# Sheet.net
KiCad netlist of a schematic drawn in Altium Designer
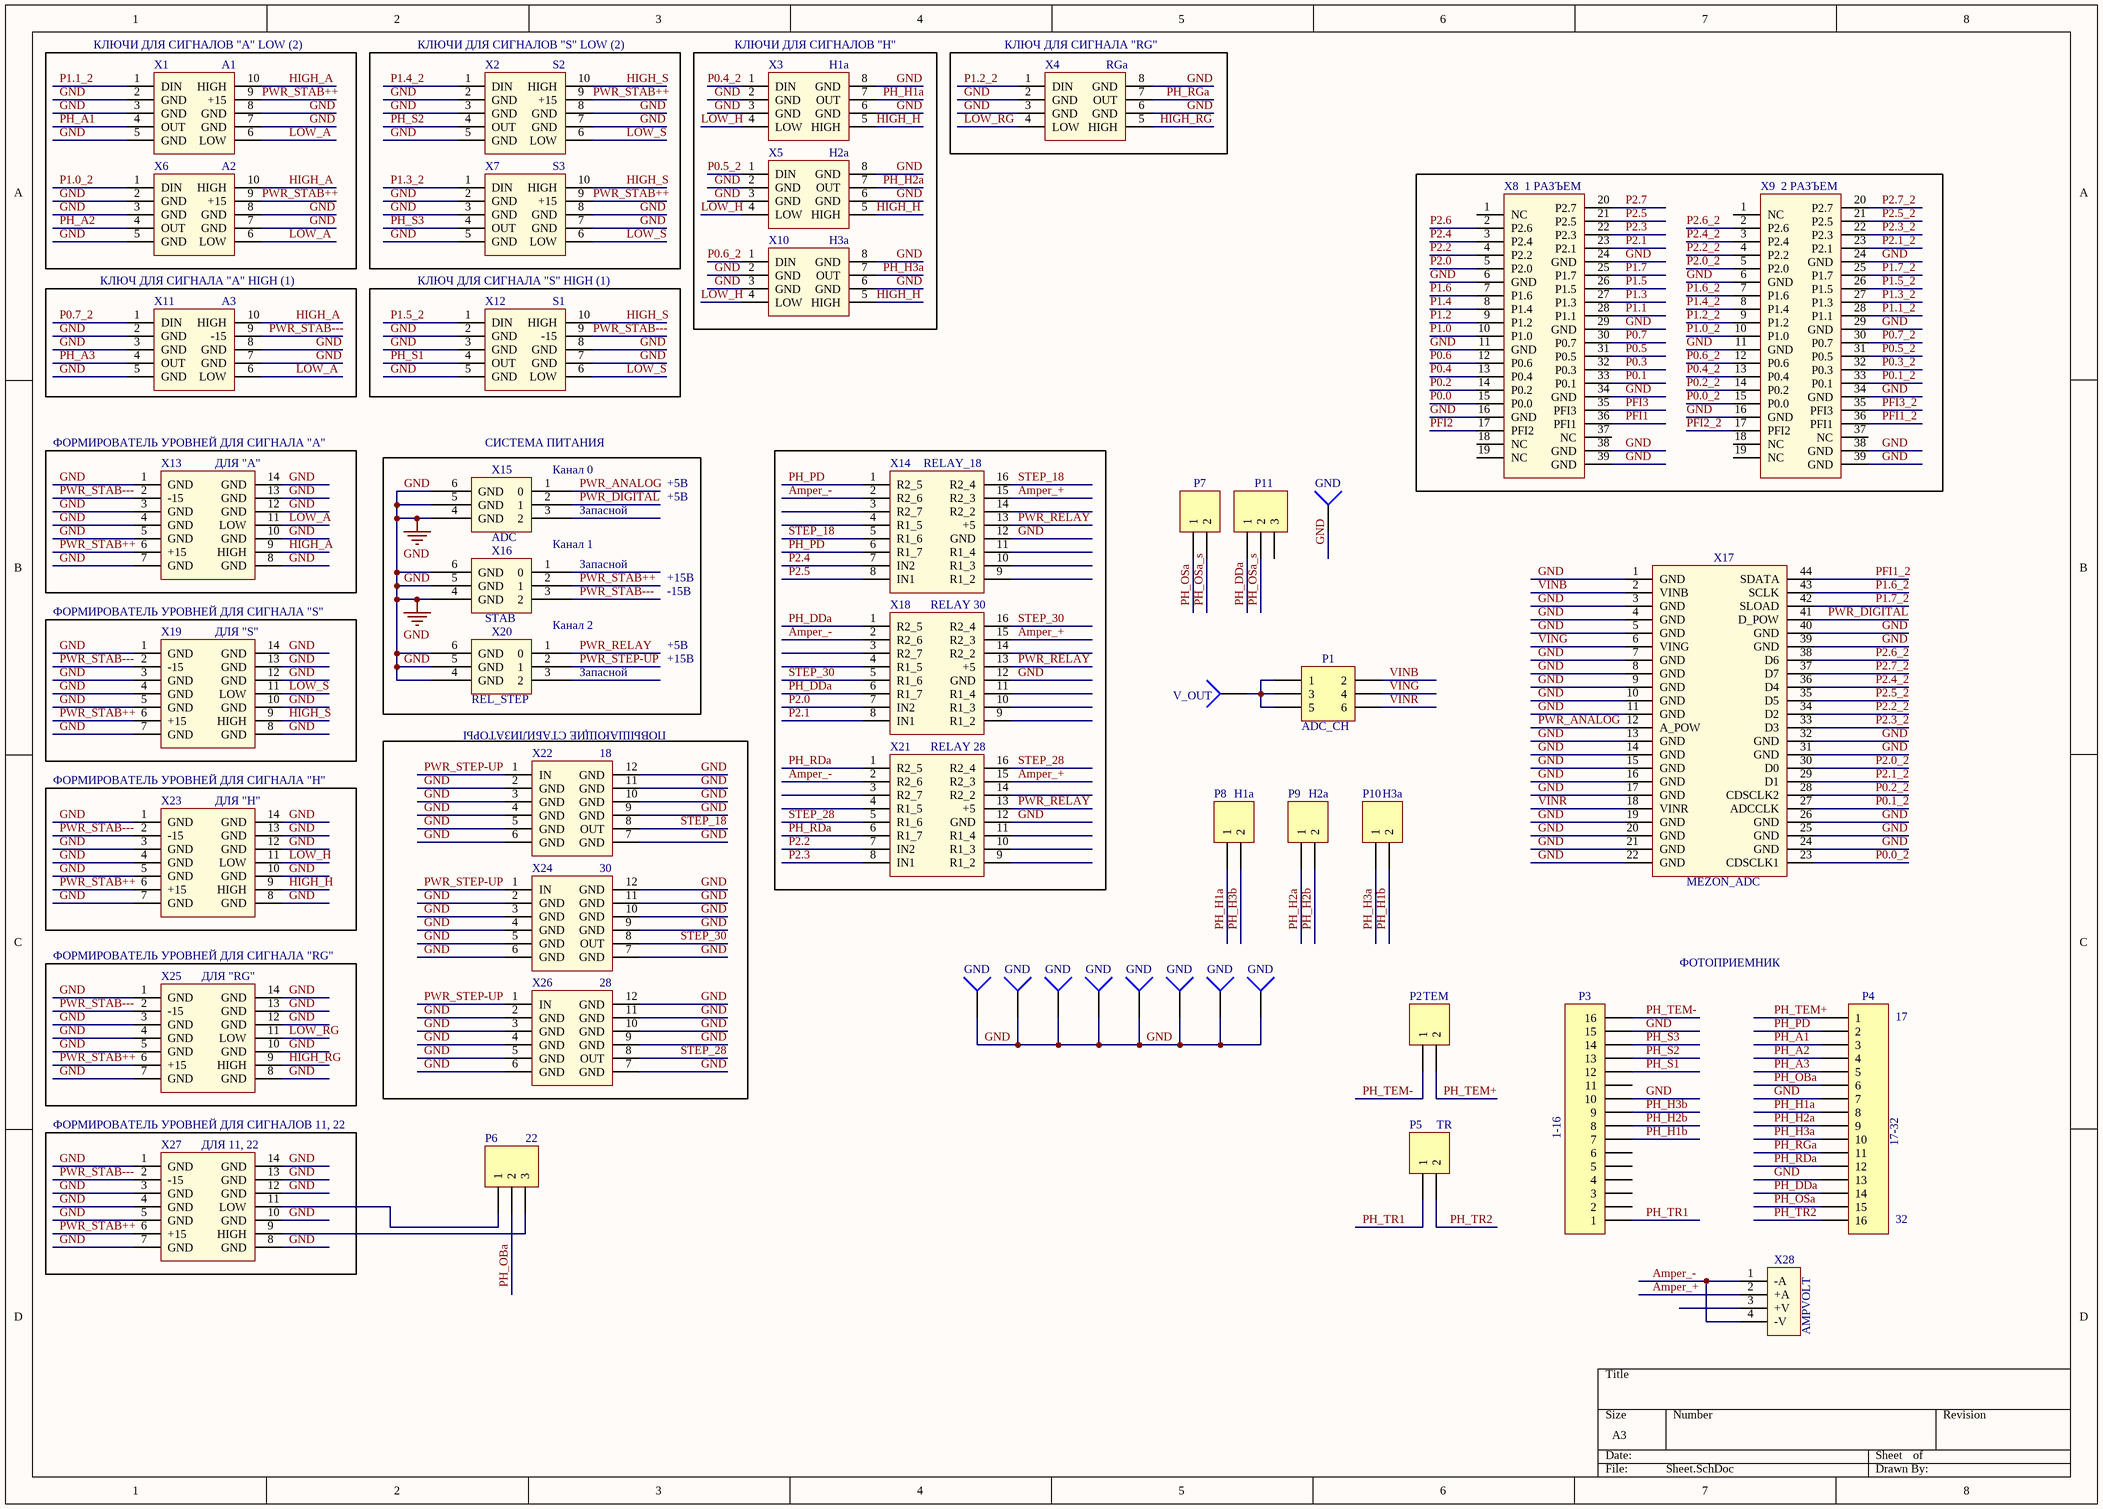
[diagram p0: Sheet.SchDoc]

(export (version "E")
  (design (tool "Eeschema 10.0.6"))
  (components
    (comp (ref "J1")
      (value "GND")
      (footprint "PIN1")
      (description "Socket")
      (fields (field (name "PUBLISHER") "Altium Limited"))
      (libsource (lib "Miscellaneous Connectors") (part "Socket"))
    )
    (comp (ref "J2")
      (value "GND")
      (footprint "PIN1")
      (description "Socket")
      (fields (field (name "PUBLISHER") "Altium Limited"))
      (libsource (lib "Miscellaneous Connectors") (part "Socket"))
    )
    (comp (ref "J3")
      (value "GND")
      (footprint "PIN1")
      (description "Socket")
      (fields (field (name "PUBLISHER") "Altium Limited"))
      (libsource (lib "Miscellaneous Connectors") (part "Socket"))
    )
    (comp (ref "J4")
      (value "GND")
      (footprint "PIN1")
      (description "Socket")
      (fields (field (name "PUBLISHER") "Altium Limited"))
      (libsource (lib "Miscellaneous Connectors") (part "Socket"))
    )
    (comp (ref "J5")
      (value "GND")
      (footprint "PIN1")
      (description "Socket")
      (fields (field (name "PUBLISHER") "Altium Limited"))
      (libsource (lib "Miscellaneous Connectors") (part "Socket"))
    )
    (comp (ref "J6")
      (value "GND")
      (footprint "PIN1")
      (description "Socket")
      (fields (field (name "PUBLISHER") "Altium Limited"))
      (libsource (lib "Miscellaneous Connectors") (part "Socket"))
    )
    (comp (ref "J7")
      (value "GND")
      (footprint "PIN1")
      (description "Socket")
      (fields (field (name "PUBLISHER") "Altium Limited"))
      (libsource (lib "Miscellaneous Connectors") (part "Socket"))
    )
    (comp (ref "J8")
      (value "GND")
      (footprint "PIN1")
      (description "Socket")
      (fields (field (name "PUBLISHER") "Altium Limited"))
      (libsource (lib "Miscellaneous Connectors") (part "Socket"))
    )
    (comp (ref "J9")
      (value "GND")
      (footprint "PIN1")
      (description "Socket")
      (fields (field (name "PUBLISHER") "Altium Limited"))
      (libsource (lib "Miscellaneous Connectors") (part "Socket"))
    )
    (comp (ref "J10")
      (value "V_OUT")
      (footprint "PIN1")
      (description "Socket")
      (fields (field (name "PUBLISHER") "Altium Limited"))
      (libsource (lib "Miscellaneous Connectors") (part "Socket"))
    )
    (comp (ref "P1")
      (value "ADC_CH")
      (footprint "HDR2X3")
      (description "Header, 3-Pin, Dual row")
      (fields (field (name "PUBLISHER") "Altium Limited"))
      (libsource (lib "Miscellaneous Connectors") (part "Header 3X2"))
    )
    (comp (ref "P2")
      (value "TEM")
      (footprint "HDR1X2")
      (description "Header, 2-Pin")
      (fields (field (name "PUBLISHER") "Altium Limited"))
      (libsource (lib "Miscellaneous Connectors") (part "Header 2"))
    )
    (comp (ref "P3")
      (value "1-16")
      (footprint "HDR1X16")
      (description "Header, 16-Pin")
      (fields (field (name "PUBLISHER") "Altium Limited"))
      (libsource (lib "Miscellaneous Connectors") (part "Header 16"))
    )
    (comp (ref "P4")
      (value "17-32")
      (footprint "HDR1X16")
      (description "Header, 16-Pin")
      (fields (field (name "PUBLISHER") "Altium Limited"))
      (libsource (lib "") (part "Header 16_1"))
    )
    (comp (ref "P5")
      (value "TR")
      (footprint "HDR1X2")
      (description "Header, 2-Pin")
      (fields (field (name "PUBLISHER") "Altium Limited"))
      (libsource (lib "Miscellaneous Connectors") (part "Header 2"))
    )
    (comp (ref "P6")
      (value "22")
      (footprint "HDR1X3")
      (description "Header, 3-Pin")
      (fields (field (name "PUBLISHER") "Altium Limited"))
      (libsource (lib "Miscellaneous Connectors") (part "Header 3"))
    )
    (comp (ref "P7")
      (value "~")
      (footprint "HDR1X2")
      (description "Header, 2-Pin")
      (fields (field (name "PUBLISHER") "Altium Limited"))
      (libsource (lib "Miscellaneous Connectors") (part "Header 2"))
    )
    (comp (ref "P8")
      (value "H1a")
      (footprint "HDR1X2")
      (description "Header, 2-Pin")
      (fields (field (name "PUBLISHER") "Altium Limited"))
      (libsource (lib "Miscellaneous Connectors") (part "Header 2"))
    )
    (comp (ref "P9")
      (value "H2a")
      (footprint "HDR1X2")
      (description "Header, 2-Pin")
      (fields (field (name "PUBLISHER") "Altium Limited"))
      (libsource (lib "Miscellaneous Connectors") (part "Header 2"))
    )
    (comp (ref "P10")
      (value "H3a")
      (footprint "HDR1X2")
      (description "Header, 2-Pin")
      (fields (field (name "PUBLISHER") "Altium Limited"))
      (libsource (lib "Miscellaneous Connectors") (part "Header 2"))
    )
    (comp (ref "P11")
      (value "~")
      (footprint "HDR1X3")
      (description "Header, 3-Pin")
      (fields (field (name "PUBLISHER") "Altium Limited"))
      (libsource (lib "Miscellaneous Connectors") (part "Header 3"))
    )
    (comp (ref "X1") (value "A1") (footprint "MEZON_V") (libsource (lib "Schlib") (part "MEZON_V_+15")))
    (comp (ref "X2") (value "S2") (footprint "MEZON_V") (libsource (lib "Schlib") (part "MEZON_V_+15")))
    (comp (ref "X3") (value "H1a") (footprint "MEZON_H") (libsource (lib "Schlib") (part "MEZON_H")))
    (comp (ref "X4") (value "RGa") (footprint "MEZON_H") (libsource (lib "Schlib") (part "MEZON_H")))
    (comp (ref "X5") (value "H2a") (footprint "MEZON_H") (libsource (lib "Schlib") (part "MEZON_H")))
    (comp (ref "X6") (value "A2") (footprint "MEZON_V") (libsource (lib "Schlib") (part "MEZON_V_+15")))
    (comp (ref "X7") (value "S3") (footprint "MEZON_V") (libsource (lib "Schlib") (part "MEZON_V_+15")))
    (comp (ref "X8")
      (value "1 РАЗЪЕМ")
      (footprint "CHEAP_CONN_FEMALE")
      (libsource (lib "Schlib") (part "CHEAP_CON_37_FEMALE"))
    )
    (comp (ref "X9")
      (value "2 РАЗЪЕМ")
      (footprint "CHEAP_CONN_FEMALE")
      (libsource (lib "Schlib") (part "CHEAP_CON_37_FEMALE"))
    )
    (comp (ref "X10") (value "H3a") (footprint "MEZON_H") (libsource (lib "Schlib") (part "MEZON_H")))
    (comp (ref "X11") (value "A3") (footprint "MEZON_V") (libsource (lib "Schlib") (part "MEZON_V")))
    (comp (ref "X12") (value "S1") (footprint "MEZON_V") (libsource (lib "Schlib") (part "MEZON_V")))
    (comp (ref "X13")
      (value "ДЛЯ \"А\"")
      (footprint "MEZON_V+H")
      (libsource (lib "Schlib") (part "MEZON_V+H"))
    )
    (comp (ref "X14")
      (value "RELAY_18")
      (footprint "RELAY_MODULE")
      (libsource (lib "Schlib") (part "MEZON_RELAY"))
    )
    (comp (ref "X15") (value "ADC") (footprint "POWER") (libsource (lib "Schlib") (part "POWER")))
    (comp (ref "X16") (value "STAB") (footprint "POWER") (libsource (lib "Schlib") (part "POWER")))
    (comp (ref "X17")
      (value "MEZON_ADC")
      (footprint "MEZON_ADC")
      (libsource (lib "Schlib") (part "MEZON_ADC"))
    )
    (comp (ref "X18")
      (value "RELAY 30")
      (footprint "RELAY_MODULE")
      (libsource (lib "Schlib") (part "MEZON_RELAY"))
    )
    (comp (ref "X19")
      (value "ДЛЯ \"S\"")
      (footprint "MEZON_V+H")
      (libsource (lib "Schlib") (part "MEZON_V+H"))
    )
    (comp (ref "X20") (value "REL_STEP") (footprint "POWER") (libsource (lib "Schlib") (part "POWER")))
    (comp (ref "X21")
      (value "RELAY 28")
      (footprint "RELAY_MODULE")
      (libsource (lib "Schlib") (part "MEZON_RELAY"))
    )
    (comp (ref "X22")
      (value "18")
      (footprint "MEZON_STEP-UP")
      (libsource (lib "Schlib") (part "MEZON_STEP-UP"))
    )
    (comp (ref "X23")
      (value "ДЛЯ \"H\"")
      (footprint "MEZON_V+H")
      (libsource (lib "Schlib") (part "MEZON_V+H"))
    )
    (comp (ref "X24")
      (value "30")
      (footprint "MEZON_STEP-UP")
      (libsource (lib "Schlib") (part "MEZON_STEP-UP"))
    )
    (comp (ref "X25")
      (value "ДЛЯ \"RG\"")
      (footprint "MEZON_V+H")
      (libsource (lib "Schlib") (part "MEZON_V+H"))
    )
    (comp (ref "X26")
      (value "28")
      (footprint "MEZON_STEP-UP")
      (libsource (lib "Schlib") (part "MEZON_STEP-UP"))
    )
    (comp (ref "X27")
      (value "ДЛЯ 11, 22")
      (footprint "MEZON_V+H")
      (libsource (lib "Schlib") (part "MEZON_V+H"))
    )
    (comp (ref "X28")
      (value "AMPVOLT")
      (footprint "AMP_VOLTMETER")
      (libsource (lib "Schlib") (part "AMP_VOLTMETER"))
    )
  )
  (nets
    (net (code "1") (name "/Amper_+") (class "Default")
      (node (ref "X14") (pin "15") (pinfunction "R2_3_15") (pintype "passive"))
      (node (ref "X18") (pin "15") (pinfunction "R2_3_15") (pintype "passive"))
      (node (ref "X21") (pin "15") (pinfunction "R2_3_15") (pintype "passive"))
      (node (ref "X28") (pin "2") (pinfunction "+A_2") (pintype "passive"))
    )
    (net (code "2") (name "/Amper_-") (class "Default")
      (node (ref "X14") (pin "2") (pinfunction "R2_6_2") (pintype "passive"))
      (node (ref "X18") (pin "2") (pinfunction "R2_6_2") (pintype "passive"))
      (node (ref "X21") (pin "2") (pinfunction "R2_6_2") (pintype "passive"))
      (node (ref "X28") (pin "1") (pinfunction "-A_1") (pintype "passive"))
      (node (ref "X28") (pin "4") (pinfunction "-V_4") (pintype "passive"))
    )
    (net (code "3") (name "/HIGH_A") (class "Default")
      (node (ref "X1") (pin "10") (pinfunction "HIGH_10") (pintype "passive"))
      (node (ref "X11") (pin "10") (pinfunction "HIGH_10") (pintype "passive"))
      (node (ref "X13") (pin "9") (pinfunction "HIGH_9") (pintype "passive"))
      (node (ref "X6") (pin "10") (pinfunction "HIGH_10") (pintype "passive"))
    )
    (net (code "4") (name "/HIGH_H") (class "Default")
      (node (ref "X10") (pin "5") (pinfunction "HIGH_5") (pintype "passive"))
      (node (ref "X23") (pin "9") (pinfunction "HIGH_9") (pintype "passive"))
      (node (ref "X3") (pin "5") (pinfunction "HIGH_5") (pintype "passive"))
      (node (ref "X5") (pin "5") (pinfunction "HIGH_5") (pintype "passive"))
    )
    (net (code "5") (name "/HIGH_RG") (class "Default")
      (node (ref "X25") (pin "9") (pinfunction "HIGH_9") (pintype "passive"))
      (node (ref "X4") (pin "5") (pinfunction "HIGH_5") (pintype "passive"))
    )
    (net (code "6") (name "/HIGH_S") (class "Default")
      (node (ref "X12") (pin "10") (pinfunction "HIGH_10") (pintype "passive"))
      (node (ref "X19") (pin "9") (pinfunction "HIGH_9") (pintype "passive"))
      (node (ref "X2") (pin "10") (pinfunction "HIGH_10") (pintype "passive"))
      (node (ref "X7") (pin "10") (pinfunction "HIGH_10") (pintype "passive"))
    )
    (net (code "7") (name "/LOW_A") (class "Default")
      (node (ref "X1") (pin "6") (pinfunction "LOW_6") (pintype "passive"))
      (node (ref "X11") (pin "6") (pinfunction "LOW_6") (pintype "passive"))
      (node (ref "X13") (pin "11") (pinfunction "LOW_11") (pintype "passive"))
      (node (ref "X6") (pin "6") (pinfunction "LOW_6") (pintype "passive"))
    )
    (net (code "8") (name "/LOW_H") (class "Default")
      (node (ref "X10") (pin "4") (pinfunction "LOW_4") (pintype "passive"))
      (node (ref "X23") (pin "11") (pinfunction "LOW_11") (pintype "passive"))
      (node (ref "X3") (pin "4") (pinfunction "LOW_4") (pintype "passive"))
      (node (ref "X5") (pin "4") (pinfunction "LOW_4") (pintype "passive"))
    )
    (net (code "9") (name "/LOW_RG") (class "Default")
      (node (ref "X25") (pin "11") (pinfunction "LOW_11") (pintype "passive"))
      (node (ref "X4") (pin "4") (pinfunction "LOW_4") (pintype "passive"))
    )
    (net (code "10") (name "/LOW_S") (class "Default")
      (node (ref "X12") (pin "6") (pinfunction "LOW_6") (pintype "passive"))
      (node (ref "X19") (pin "11") (pinfunction "LOW_11") (pintype "passive"))
      (node (ref "X2") (pin "6") (pinfunction "LOW_6") (pintype "passive"))
      (node (ref "X7") (pin "6") (pinfunction "LOW_6") (pintype "passive"))
    )
    (net (code "11") (name "/P0.0") (class "Default")
      (node (ref "X8") (pin "15") (pinfunction "P0.0_15") (pintype "passive"))
    )
    (net (code "12") (name "/P0.0_2") (class "Default")
      (node (ref "X17") (pin "23") (pinfunction "CDSCLK1_23") (pintype "passive"))
      (node (ref "X9") (pin "15") (pinfunction "P0.0_15") (pintype "passive"))
    )
    (net (code "13") (name "/P0.1") (class "Default")
      (node (ref "X8") (pin "33") (pinfunction "P0.1_33") (pintype "passive"))
    )
    (net (code "14") (name "/P0.1_2") (class "Default")
      (node (ref "X17") (pin "27") (pinfunction "ADCCLK_27") (pintype "passive"))
      (node (ref "X9") (pin "33") (pinfunction "P0.1_33") (pintype "passive"))
    )
    (net (code "15") (name "/P0.2") (class "Default")
      (node (ref "X8") (pin "14") (pinfunction "P0.2_14") (pintype "passive"))
    )
    (net (code "16") (name "/P0.2_2") (class "Default")
      (node (ref "X17") (pin "28") (pinfunction "CDSCLK2_28") (pintype "passive"))
      (node (ref "X9") (pin "14") (pinfunction "P0.2_14") (pintype "passive"))
    )
    (net (code "17") (name "/P0.3") (class "Default")
      (node (ref "X8") (pin "32") (pinfunction "P0.3_32") (pintype "passive"))
    )
    (net (code "18") (name "/P0.3_2") (class "Default")
      (node (ref "X9") (pin "32") (pinfunction "P0.3_32") (pintype "passive"))
    )
    (net (code "19") (name "/P0.4") (class "Default")
      (node (ref "X8") (pin "13") (pinfunction "P0.4_13") (pintype "passive"))
    )
    (net (code "20") (name "/P0.4_2") (class "Default")
      (node (ref "X3") (pin "1") (pinfunction "DIN_1") (pintype "passive"))
      (node (ref "X9") (pin "13") (pinfunction "P0.4_13") (pintype "passive"))
    )
    (net (code "21") (name "/P0.5") (class "Default")
      (node (ref "X8") (pin "31") (pinfunction "P0.5_31") (pintype "passive"))
    )
    (net (code "22") (name "/P0.5_2") (class "Default")
      (node (ref "X5") (pin "1") (pinfunction "DIN_1") (pintype "passive"))
      (node (ref "X9") (pin "31") (pinfunction "P0.5_31") (pintype "passive"))
    )
    (net (code "23") (name "/P0.6") (class "Default")
      (node (ref "X8") (pin "12") (pinfunction "P0.6_12") (pintype "passive"))
    )
    (net (code "24") (name "/P0.6_2") (class "Default")
      (node (ref "X10") (pin "1") (pinfunction "DIN_1") (pintype "passive"))
      (node (ref "X9") (pin "12") (pinfunction "P0.6_12") (pintype "passive"))
    )
    (net (code "25") (name "/P0.7") (class "Default")
      (node (ref "X8") (pin "30") (pinfunction "P0.7_30") (pintype "passive"))
    )
    (net (code "26") (name "/P0.7_2") (class "Default")
      (node (ref "X11") (pin "1") (pinfunction "DIN_1") (pintype "passive"))
      (node (ref "X9") (pin "30") (pinfunction "P0.7_30") (pintype "passive"))
    )
    (net (code "27") (name "/P1.0") (class "Default")
      (node (ref "X8") (pin "10") (pinfunction "P1.0_10") (pintype "passive"))
    )
    (net (code "28") (name "/P1.0_2") (class "Default")
      (node (ref "X6") (pin "1") (pinfunction "DIN_1") (pintype "passive"))
      (node (ref "X9") (pin "10") (pinfunction "P1.0_10") (pintype "passive"))
    )
    (net (code "29") (name "/P1.1") (class "Default")
      (node (ref "X8") (pin "28") (pinfunction "P1.1_28") (pintype "passive"))
    )
    (net (code "30") (name "/P1.1_2") (class "Default")
      (node (ref "X1") (pin "1") (pinfunction "DIN_1") (pintype "passive"))
      (node (ref "X9") (pin "28") (pinfunction "P1.1_28") (pintype "passive"))
    )
    (net (code "31") (name "/P1.2") (class "Default")
      (node (ref "X8") (pin "9") (pinfunction "P1.2_9") (pintype "passive"))
    )
    (net (code "32") (name "/P1.2_2") (class "Default")
      (node (ref "X4") (pin "1") (pinfunction "DIN_1") (pintype "passive"))
      (node (ref "X9") (pin "9") (pinfunction "P1.2_9") (pintype "passive"))
    )
    (net (code "33") (name "/P1.3") (class "Default")
      (node (ref "X8") (pin "27") (pinfunction "P1.3_27") (pintype "passive"))
    )
    (net (code "34") (name "/P1.3_2") (class "Default")
      (node (ref "X7") (pin "1") (pinfunction "DIN_1") (pintype "passive"))
      (node (ref "X9") (pin "27") (pinfunction "P1.3_27") (pintype "passive"))
    )
    (net (code "35") (name "/P1.4") (class "Default")
      (node (ref "X8") (pin "8") (pinfunction "P1.4_8") (pintype "passive"))
    )
    (net (code "36") (name "/P1.4_2") (class "Default")
      (node (ref "X2") (pin "1") (pinfunction "DIN_1") (pintype "passive"))
      (node (ref "X9") (pin "8") (pinfunction "P1.4_8") (pintype "passive"))
    )
    (net (code "37") (name "/P1.5") (class "Default")
      (node (ref "X8") (pin "26") (pinfunction "P1.5_26") (pintype "passive"))
    )
    (net (code "38") (name "/P1.5_2") (class "Default")
      (node (ref "X12") (pin "1") (pinfunction "DIN_1") (pintype "passive"))
      (node (ref "X9") (pin "26") (pinfunction "P1.5_26") (pintype "passive"))
    )
    (net (code "39") (name "/P1.6") (class "Default")
      (node (ref "X8") (pin "7") (pinfunction "P1.6_7") (pintype "passive"))
    )
    (net (code "40") (name "/P1.6_2") (class "Default")
      (node (ref "X17") (pin "43") (pinfunction "SCLK_43") (pintype "passive"))
      (node (ref "X9") (pin "7") (pinfunction "P1.6_7") (pintype "passive"))
    )
    (net (code "41") (name "/P1.7") (class "Default")
      (node (ref "X8") (pin "25") (pinfunction "P1.7_25") (pintype "passive"))
    )
    (net (code "42") (name "/P1.7_2") (class "Default")
      (node (ref "X17") (pin "42") (pinfunction "SLOAD_42") (pintype "passive"))
      (node (ref "X9") (pin "25") (pinfunction "P1.7_25") (pintype "passive"))
    )
    (net (code "43") (name "/P2.0") (class "Default")
      (node (ref "X18") (pin "7") (pinfunction "IN2_7") (pintype "passive"))
      (node (ref "X8") (pin "5") (pinfunction "P2.0_5") (pintype "passive"))
    )
    (net (code "44") (name "/P2.0_2") (class "Default")
      (node (ref "X17") (pin "30") (pinfunction "D0_30") (pintype "passive"))
      (node (ref "X9") (pin "5") (pinfunction "P2.0_5") (pintype "passive"))
    )
    (net (code "45") (name "/P2.1") (class "Default")
      (node (ref "X18") (pin "8") (pinfunction "IN1_8") (pintype "passive"))
      (node (ref "X8") (pin "23") (pinfunction "P2.1_23") (pintype "passive"))
    )
    (net (code "46") (name "/P2.1_2") (class "Default")
      (node (ref "X17") (pin "29") (pinfunction "D1_29") (pintype "passive"))
      (node (ref "X9") (pin "23") (pinfunction "P2.1_23") (pintype "passive"))
    )
    (net (code "47") (name "/P2.2") (class "Default")
      (node (ref "X21") (pin "7") (pinfunction "IN2_7") (pintype "passive"))
      (node (ref "X8") (pin "4") (pinfunction "P2.2_4") (pintype "passive"))
    )
    (net (code "48") (name "/P2.2_2") (class "Default")
      (node (ref "X17") (pin "34") (pinfunction "D2_34") (pintype "passive"))
      (node (ref "X9") (pin "4") (pinfunction "P2.2_4") (pintype "passive"))
    )
    (net (code "49") (name "/P2.3") (class "Default")
      (node (ref "X21") (pin "8") (pinfunction "IN1_8") (pintype "passive"))
      (node (ref "X8") (pin "22") (pinfunction "P2.3_22") (pintype "passive"))
    )
    (net (code "50") (name "/P2.3_2") (class "Default")
      (node (ref "X17") (pin "33") (pinfunction "D3_33") (pintype "passive"))
      (node (ref "X9") (pin "22") (pinfunction "P2.3_22") (pintype "passive"))
    )
    (net (code "51") (name "/P2.4") (class "Default")
      (node (ref "X14") (pin "7") (pinfunction "IN2_7") (pintype "passive"))
      (node (ref "X8") (pin "3") (pinfunction "P2.4_3") (pintype "passive"))
    )
    (net (code "52") (name "/P2.4_2") (class "Default")
      (node (ref "X17") (pin "36") (pinfunction "D4_36") (pintype "passive"))
      (node (ref "X9") (pin "3") (pinfunction "P2.4_3") (pintype "passive"))
    )
    (net (code "53") (name "/P2.5") (class "Default")
      (node (ref "X14") (pin "8") (pinfunction "IN1_8") (pintype "passive"))
      (node (ref "X8") (pin "21") (pinfunction "P2.5_21") (pintype "passive"))
    )
    (net (code "54") (name "/P2.5_2") (class "Default")
      (node (ref "X17") (pin "35") (pinfunction "D5_35") (pintype "passive"))
      (node (ref "X9") (pin "21") (pinfunction "P2.5_21") (pintype "passive"))
    )
    (net (code "55") (name "/P2.6") (class "Default")
      (node (ref "X8") (pin "2") (pinfunction "P2.6_2") (pintype "passive"))
    )
    (net (code "56") (name "/P2.6_2") (class "Default")
      (node (ref "X17") (pin "38") (pinfunction "D6_38") (pintype "passive"))
      (node (ref "X9") (pin "2") (pinfunction "P2.6_2") (pintype "passive"))
    )
    (net (code "57") (name "/P2.7") (class "Default")
      (node (ref "X8") (pin "20") (pinfunction "P2.7_20") (pintype "passive"))
    )
    (net (code "58") (name "/P2.7_2") (class "Default")
      (node (ref "X17") (pin "37") (pinfunction "D7_37") (pintype "passive"))
      (node (ref "X9") (pin "20") (pinfunction "P2.7_20") (pintype "passive"))
    )
    (net (code "59") (name "/PFI1") (class "Default")
      (node (ref "X8") (pin "36") (pinfunction "PFI1_36") (pintype "passive"))
    )
    (net (code "60") (name "/PFI1_2") (class "Default")
      (node (ref "X17") (pin "44") (pinfunction "SDATA_44") (pintype "passive"))
      (node (ref "X9") (pin "36") (pinfunction "PFI1_36") (pintype "passive"))
    )
    (net (code "61") (name "/PFI2") (class "Default")
      (node (ref "X8") (pin "17") (pinfunction "PFI2_17") (pintype "passive"))
    )
    (net (code "62") (name "/PFI2_2") (class "Default")
      (node (ref "X9") (pin "17") (pinfunction "PFI2_17") (pintype "passive"))
    )
    (net (code "63") (name "/PFI3") (class "Default")
      (node (ref "X8") (pin "35") (pinfunction "PFI3_35") (pintype "passive"))
    )
    (net (code "64") (name "/PFI3_2") (class "Default")
      (node (ref "X9") (pin "35") (pinfunction "PFI3_35") (pintype "passive"))
    )
    (net (code "65") (name "/PH_A1") (class "Default")
      (node (ref "P4") (pin "3") (pinfunction "3_3") (pintype "passive"))
      (node (ref "X1") (pin "4") (pinfunction "OUT_4") (pintype "passive"))
    )
    (net (code "66") (name "/PH_A2") (class "Default")
      (node (ref "P4") (pin "4") (pinfunction "4_4") (pintype "passive"))
      (node (ref "X6") (pin "4") (pinfunction "OUT_4") (pintype "passive"))
    )
    (net (code "67") (name "/PH_A3") (class "Default")
      (node (ref "P4") (pin "5") (pinfunction "5_5") (pintype "passive"))
      (node (ref "X11") (pin "4") (pinfunction "OUT_4") (pintype "passive"))
    )
    (net (code "68") (name "/PH_DDa") (class "Default")
      (node (ref "P11") (pin "1") (pinfunction "1_1") (pintype "passive"))
      (node (ref "P4") (pin "14") (pinfunction "14_14") (pintype "passive"))
      (node (ref "X18") (pin "1") (pinfunction "R2_5_1") (pintype "passive"))
      (node (ref "X18") (pin "6") (pinfunction "R1_7_6") (pintype "passive"))
    )
    (net (code "69") (name "/PH_H1a") (class "Default")
      (node (ref "P4") (pin "8") (pinfunction "8_8") (pintype "passive"))
      (node (ref "P8") (pin "1") (pinfunction "1_1") (pintype "passive"))
      (node (ref "X3") (pin "7") (pinfunction "OUT_7") (pintype "passive"))
    )
    (net (code "70") (name "/PH_H1b") (class "Default")
      (node (ref "P10") (pin "2") (pinfunction "2_2") (pintype "passive"))
      (node (ref "P3") (pin "7") (pinfunction "7_7") (pintype "passive"))
    )
    (net (code "71") (name "/PH_H2a") (class "Default")
      (node (ref "P4") (pin "9") (pinfunction "9_9") (pintype "passive"))
      (node (ref "P9") (pin "1") (pinfunction "1_1") (pintype "passive"))
      (node (ref "X5") (pin "7") (pinfunction "OUT_7") (pintype "passive"))
    )
    (net (code "72") (name "/PH_H2b") (class "Default")
      (node (ref "P3") (pin "8") (pinfunction "8_8") (pintype "passive"))
      (node (ref "P9") (pin "2") (pinfunction "2_2") (pintype "passive"))
    )
    (net (code "73") (name "/PH_H3a") (class "Default")
      (node (ref "P10") (pin "1") (pinfunction "1_1") (pintype "passive"))
      (node (ref "P4") (pin "10") (pinfunction "10_10") (pintype "passive"))
      (node (ref "X10") (pin "7") (pinfunction "OUT_7") (pintype "passive"))
    )
    (net (code "74") (name "/PH_H3b") (class "Default")
      (node (ref "P3") (pin "9") (pinfunction "9_9") (pintype "passive"))
      (node (ref "P8") (pin "2") (pinfunction "2_2") (pintype "passive"))
    )
    (net (code "75") (name "/PH_OBa") (class "Default")
      (node (ref "P4") (pin "6") (pinfunction "6_6") (pintype "passive"))
      (node (ref "P6") (pin "2") (pinfunction "2_2") (pintype "passive"))
    )
    (net (code "76") (name "/PH_OSa") (class "Default")
      (node (ref "P4") (pin "15") (pinfunction "15_15") (pintype "passive"))
      (node (ref "P7") (pin "1") (pinfunction "1_1") (pintype "passive"))
    )
    (net (code "77") (name "/PH_OSa_s") (class "Default")
      (node (ref "P11") (pin "2") (pinfunction "2_2") (pintype "passive"))
      (node (ref "P7") (pin "2") (pinfunction "2_2") (pintype "passive"))
    )
    (net (code "78") (name "/PH_PD") (class "Default")
      (node (ref "P4") (pin "2") (pinfunction "2_2") (pintype "passive"))
      (node (ref "X14") (pin "1") (pinfunction "R2_5_1") (pintype "passive"))
      (node (ref "X14") (pin "6") (pinfunction "R1_7_6") (pintype "passive"))
    )
    (net (code "79") (name "/PH_RDa") (class "Default")
      (node (ref "P4") (pin "12") (pinfunction "12_12") (pintype "passive"))
      (node (ref "X21") (pin "1") (pinfunction "R2_5_1") (pintype "passive"))
      (node (ref "X21") (pin "6") (pinfunction "R1_7_6") (pintype "passive"))
    )
    (net (code "80") (name "/PH_RGa") (class "Default")
      (node (ref "P4") (pin "11") (pinfunction "11_11") (pintype "passive"))
      (node (ref "X4") (pin "7") (pinfunction "OUT_7") (pintype "passive"))
    )
    (net (code "81") (name "/PH_S1") (class "Default")
      (node (ref "P3") (pin "12") (pinfunction "12_12") (pintype "passive"))
      (node (ref "X12") (pin "4") (pinfunction "OUT_4") (pintype "passive"))
    )
    (net (code "82") (name "/PH_S2") (class "Default")
      (node (ref "P3") (pin "13") (pinfunction "13_13") (pintype "passive"))
      (node (ref "X2") (pin "4") (pinfunction "OUT_4") (pintype "passive"))
    )
    (net (code "83") (name "/PH_S3") (class "Default")
      (node (ref "P3") (pin "14") (pinfunction "14_14") (pintype "passive"))
      (node (ref "X7") (pin "4") (pinfunction "OUT_4") (pintype "passive"))
    )
    (net (code "84") (name "/PH_TEM+") (class "Default")
      (node (ref "P2") (pin "2") (pinfunction "2_2") (pintype "passive"))
      (node (ref "P4") (pin "1") (pinfunction "1_1") (pintype "passive"))
    )
    (net (code "85") (name "/PH_TEM-") (class "Default")
      (node (ref "P2") (pin "1") (pinfunction "1_1") (pintype "passive"))
      (node (ref "P3") (pin "16") (pinfunction "16_16") (pintype "passive"))
    )
    (net (code "86") (name "/PH_TR1") (class "Default")
      (node (ref "P3") (pin "1") (pinfunction "1_1") (pintype "passive"))
      (node (ref "P5") (pin "1") (pinfunction "1_1") (pintype "passive"))
    )
    (net (code "87") (name "/PH_TR2") (class "Default")
      (node (ref "P4") (pin "16") (pinfunction "16_16") (pintype "passive"))
      (node (ref "P5") (pin "2") (pinfunction "2_2") (pintype "passive"))
    )
    (net (code "88") (name "/PWR_ANALOG") (class "Default")
      (node (ref "X15") (pin "1") (pinfunction "0_1") (pintype "passive"))
      (node (ref "X17") (pin "12") (pinfunction "A_POW_12") (pintype "passive"))
    )
    (net (code "89") (name "/PWR_DIGITAL") (class "Default")
      (node (ref "X15") (pin "2") (pinfunction "1_2") (pintype "passive"))
      (node (ref "X17") (pin "41") (pinfunction "D_POW_41") (pintype "passive"))
    )
    (net (code "90") (name "/PWR_RELAY") (class "Default")
      (node (ref "X14") (pin "13") (pinfunction "+5_13") (pintype "passive"))
      (node (ref "X18") (pin "13") (pinfunction "+5_13") (pintype "passive"))
      (node (ref "X20") (pin "1") (pinfunction "0_1") (pintype "passive"))
      (node (ref "X21") (pin "13") (pinfunction "+5_13") (pintype "passive"))
    )
    (net (code "91") (name "/PWR_STAB++") (class "Default")
      (node (ref "X1") (pin "9") (pinfunction "+15_9") (pintype "passive"))
      (node (ref "X13") (pin "6") (pinfunction "+15_6") (pintype "passive"))
      (node (ref "X16") (pin "2") (pinfunction "1_2") (pintype "passive"))
      (node (ref "X19") (pin "6") (pinfunction "+15_6") (pintype "passive"))
      (node (ref "X2") (pin "9") (pinfunction "+15_9") (pintype "passive"))
      (node (ref "X23") (pin "6") (pinfunction "+15_6") (pintype "passive"))
      (node (ref "X25") (pin "6") (pinfunction "+15_6") (pintype "passive"))
      (node (ref "X27") (pin "6") (pinfunction "+15_6") (pintype "passive"))
      (node (ref "X6") (pin "9") (pinfunction "+15_9") (pintype "passive"))
      (node (ref "X7") (pin "9") (pinfunction "+15_9") (pintype "passive"))
    )
    (net (code "92") (name "/PWR_STAB---") (class "Default")
      (node (ref "X11") (pin "9") (pinfunction "-15_9") (pintype "passive"))
      (node (ref "X12") (pin "9") (pinfunction "-15_9") (pintype "passive"))
      (node (ref "X13") (pin "2") (pinfunction "-15_2") (pintype "passive"))
      (node (ref "X16") (pin "3") (pinfunction "2_3") (pintype "passive"))
      (node (ref "X19") (pin "2") (pinfunction "-15_2") (pintype "passive"))
      (node (ref "X23") (pin "2") (pinfunction "-15_2") (pintype "passive"))
      (node (ref "X25") (pin "2") (pinfunction "-15_2") (pintype "passive"))
      (node (ref "X27") (pin "2") (pinfunction "-15_2") (pintype "passive"))
    )
    (net (code "93") (name "/PWR_STEP-UP") (class "Default")
      (node (ref "X20") (pin "2") (pinfunction "1_2") (pintype "passive"))
      (node (ref "X22") (pin "1") (pinfunction "IN_1") (pintype "passive"))
      (node (ref "X24") (pin "1") (pinfunction "IN_1") (pintype "passive"))
      (node (ref "X26") (pin "1") (pinfunction "IN_1") (pintype "passive"))
    )
    (net (code "94") (name "/STEP_18") (class "Default")
      (node (ref "X14") (pin "16") (pinfunction "R2_4_16") (pintype "passive"))
      (node (ref "X14") (pin "5") (pinfunction "R1_6_5") (pintype "passive"))
      (node (ref "X22") (pin "8") (pinfunction "OUT_8") (pintype "passive"))
    )
    (net (code "95") (name "/STEP_28") (class "Default")
      (node (ref "X21") (pin "16") (pinfunction "R2_4_16") (pintype "passive"))
      (node (ref "X21") (pin "5") (pinfunction "R1_6_5") (pintype "passive"))
      (node (ref "X26") (pin "8") (pinfunction "OUT_8") (pintype "passive"))
    )
    (net (code "96") (name "/STEP_30") (class "Default")
      (node (ref "X18") (pin "16") (pinfunction "R2_4_16") (pintype "passive"))
      (node (ref "X18") (pin "5") (pinfunction "R1_6_5") (pintype "passive"))
      (node (ref "X24") (pin "8") (pinfunction "OUT_8") (pintype "passive"))
    )
    (net (code "97") (name "/VINB") (class "Default")
      (node (ref "P1") (pin "2") (pinfunction "2_2") (pintype "passive"))
      (node (ref "X17") (pin "2") (pinfunction "VINB_2") (pintype "passive"))
    )
    (net (code "98") (name "/VING") (class "Default")
      (node (ref "P1") (pin "4") (pinfunction "4_4") (pintype "passive"))
      (node (ref "X17") (pin "6") (pinfunction "VING_6") (pintype "passive"))
    )
    (net (code "99") (name "/VINR") (class "Default")
      (node (ref "P1") (pin "6") (pinfunction "6_6") (pintype "passive"))
      (node (ref "X17") (pin "18") (pinfunction "VINR_18") (pintype "passive"))
    )
    (net (code "100") (name "GND") (class "Default")
      (node (ref "J1") (pin "1") (pinfunction "1_1") (pintype "passive"))
      (node (ref "J2") (pin "1") (pinfunction "1_1") (pintype "passive"))
      (node (ref "J3") (pin "1") (pinfunction "1_1") (pintype "passive"))
      (node (ref "J4") (pin "1") (pinfunction "1_1") (pintype "passive"))
      (node (ref "J5") (pin "1") (pinfunction "1_1") (pintype "passive"))
      (node (ref "J6") (pin "1") (pinfunction "1_1") (pintype "passive"))
      (node (ref "J7") (pin "1") (pinfunction "1_1") (pintype "passive"))
      (node (ref "J8") (pin "1") (pinfunction "1_1") (pintype "passive"))
      (node (ref "J9") (pin "1") (pinfunction "1_1") (pintype "passive"))
      (node (ref "P3") (pin "10") (pinfunction "10_10") (pintype "passive"))
      (node (ref "P3") (pin "15") (pinfunction "15_15") (pintype "passive"))
      (node (ref "P4") (pin "13") (pinfunction "13_13") (pintype "passive"))
      (node (ref "P4") (pin "7") (pinfunction "7_7") (pintype "passive"))
      (node (ref "X1") (pin "2") (pinfunction "GND_2") (pintype "passive"))
      (node (ref "X1") (pin "3") (pinfunction "GND_3") (pintype "passive"))
      (node (ref "X1") (pin "5") (pinfunction "GND_5") (pintype "passive"))
      (node (ref "X1") (pin "7") (pinfunction "GND_7") (pintype "passive"))
      (node (ref "X1") (pin "8") (pinfunction "GND_8") (pintype "passive"))
      (node (ref "X10") (pin "2") (pinfunction "GND_2") (pintype "passive"))
      (node (ref "X10") (pin "3") (pinfunction "GND_3") (pintype "passive"))
      (node (ref "X10") (pin "6") (pinfunction "GND_6") (pintype "passive"))
      (node (ref "X10") (pin "8") (pinfunction "GND_8") (pintype "passive"))
      (node (ref "X11") (pin "2") (pinfunction "GND_2") (pintype "passive"))
      (node (ref "X11") (pin "3") (pinfunction "GND_3") (pintype "passive"))
      (node (ref "X11") (pin "5") (pinfunction "GND_5") (pintype "passive"))
      (node (ref "X11") (pin "7") (pinfunction "GND_7") (pintype "passive"))
      (node (ref "X11") (pin "8") (pinfunction "GND_8") (pintype "passive"))
      (node (ref "X12") (pin "2") (pinfunction "GND_2") (pintype "passive"))
      (node (ref "X12") (pin "3") (pinfunction "GND_3") (pintype "passive"))
      (node (ref "X12") (pin "5") (pinfunction "GND_5") (pintype "passive"))
      (node (ref "X12") (pin "7") (pinfunction "GND_7") (pintype "passive"))
      (node (ref "X12") (pin "8") (pinfunction "GND_8") (pintype "passive"))
      (node (ref "X13") (pin "1") (pinfunction "GND_1") (pintype "passive"))
      (node (ref "X13") (pin "10") (pinfunction "GND_10") (pintype "passive"))
      (node (ref "X13") (pin "12") (pinfunction "GND_12") (pintype "passive"))
      (node (ref "X13") (pin "13") (pinfunction "GND_13") (pintype "passive"))
      (node (ref "X13") (pin "14") (pinfunction "GND_14") (pintype "passive"))
      (node (ref "X13") (pin "3") (pinfunction "GND_3") (pintype "passive"))
      (node (ref "X13") (pin "4") (pinfunction "GND_4") (pintype "passive"))
      (node (ref "X13") (pin "5") (pinfunction "GND_5") (pintype "passive"))
      (node (ref "X13") (pin "7") (pinfunction "GND_7") (pintype "passive"))
      (node (ref "X13") (pin "8") (pinfunction "GND_8") (pintype "passive"))
      (node (ref "X14") (pin "12") (pinfunction "GND_12") (pintype "passive"))
      (node (ref "X15") (pin "4") (pinfunction "GND_4") (pintype "passive"))
      (node (ref "X15") (pin "5") (pinfunction "GND_5") (pintype "passive"))
      (node (ref "X15") (pin "6") (pinfunction "GND_6") (pintype "passive"))
      (node (ref "X16") (pin "4") (pinfunction "GND_4") (pintype "passive"))
      (node (ref "X16") (pin "5") (pinfunction "GND_5") (pintype "passive"))
      (node (ref "X16") (pin "6") (pinfunction "GND_6") (pintype "passive"))
      (node (ref "X17") (pin "1") (pinfunction "GND_1") (pintype "passive"))
      (node (ref "X17") (pin "10") (pinfunction "GND_10") (pintype "passive"))
      (node (ref "X17") (pin "11") (pinfunction "GND_11") (pintype "passive"))
      (node (ref "X17") (pin "13") (pinfunction "GND_13") (pintype "passive"))
      (node (ref "X17") (pin "14") (pinfunction "GND_14") (pintype "passive"))
      (node (ref "X17") (pin "15") (pinfunction "GND_15") (pintype "passive"))
      (node (ref "X17") (pin "16") (pinfunction "GND_16") (pintype "passive"))
      (node (ref "X17") (pin "17") (pinfunction "GND_17") (pintype "passive"))
      (node (ref "X17") (pin "19") (pinfunction "GND_19") (pintype "passive"))
      (node (ref "X17") (pin "20") (pinfunction "GND_20") (pintype "passive"))
      (node (ref "X17") (pin "21") (pinfunction "GND_21") (pintype "passive"))
      (node (ref "X17") (pin "22") (pinfunction "GND_22") (pintype "passive"))
      (node (ref "X17") (pin "24") (pinfunction "GND_24") (pintype "passive"))
      (node (ref "X17") (pin "25") (pinfunction "GND_25") (pintype "passive"))
      (node (ref "X17") (pin "26") (pinfunction "GND_26") (pintype "passive"))
      (node (ref "X17") (pin "3") (pinfunction "GND_3") (pintype "passive"))
      (node (ref "X17") (pin "31") (pinfunction "GND_31") (pintype "passive"))
      (node (ref "X17") (pin "32") (pinfunction "GND_32") (pintype "passive"))
      (node (ref "X17") (pin "39") (pinfunction "GND_39") (pintype "passive"))
      (node (ref "X17") (pin "4") (pinfunction "GND_4") (pintype "passive"))
      (node (ref "X17") (pin "40") (pinfunction "GND_40") (pintype "passive"))
      (node (ref "X17") (pin "5") (pinfunction "GND_5") (pintype "passive"))
      (node (ref "X17") (pin "7") (pinfunction "GND_7") (pintype "passive"))
      (node (ref "X17") (pin "8") (pinfunction "GND_8") (pintype "passive"))
      (node (ref "X17") (pin "9") (pinfunction "GND_9") (pintype "passive"))
      (node (ref "X18") (pin "12") (pinfunction "GND_12") (pintype "passive"))
      (node (ref "X19") (pin "1") (pinfunction "GND_1") (pintype "passive"))
      (node (ref "X19") (pin "10") (pinfunction "GND_10") (pintype "passive"))
      (node (ref "X19") (pin "12") (pinfunction "GND_12") (pintype "passive"))
      (node (ref "X19") (pin "13") (pinfunction "GND_13") (pintype "passive"))
      (node (ref "X19") (pin "14") (pinfunction "GND_14") (pintype "passive"))
      (node (ref "X19") (pin "3") (pinfunction "GND_3") (pintype "passive"))
      (node (ref "X19") (pin "4") (pinfunction "GND_4") (pintype "passive"))
      (node (ref "X19") (pin "5") (pinfunction "GND_5") (pintype "passive"))
      (node (ref "X19") (pin "7") (pinfunction "GND_7") (pintype "passive"))
      (node (ref "X19") (pin "8") (pinfunction "GND_8") (pintype "passive"))
      (node (ref "X2") (pin "2") (pinfunction "GND_2") (pintype "passive"))
      (node (ref "X2") (pin "3") (pinfunction "GND_3") (pintype "passive"))
      (node (ref "X2") (pin "5") (pinfunction "GND_5") (pintype "passive"))
      (node (ref "X2") (pin "7") (pinfunction "GND_7") (pintype "passive"))
      (node (ref "X2") (pin "8") (pinfunction "GND_8") (pintype "passive"))
      (node (ref "X20") (pin "4") (pinfunction "GND_4") (pintype "passive"))
      (node (ref "X20") (pin "5") (pinfunction "GND_5") (pintype "passive"))
      (node (ref "X20") (pin "6") (pinfunction "GND_6") (pintype "passive"))
      (node (ref "X21") (pin "12") (pinfunction "GND_12") (pintype "passive"))
      (node (ref "X22") (pin "10") (pinfunction "GND_10") (pintype "passive"))
      (node (ref "X22") (pin "11") (pinfunction "GND_11") (pintype "passive"))
      (node (ref "X22") (pin "12") (pinfunction "GND_12") (pintype "passive"))
      (node (ref "X22") (pin "2") (pinfunction "GND_2") (pintype "passive"))
      (node (ref "X22") (pin "3") (pinfunction "GND_3") (pintype "passive"))
      (node (ref "X22") (pin "4") (pinfunction "GND_4") (pintype "passive"))
      (node (ref "X22") (pin "5") (pinfunction "GND_5") (pintype "passive"))
      (node (ref "X22") (pin "6") (pinfunction "GND_6") (pintype "passive"))
      (node (ref "X22") (pin "7") (pinfunction "GND_7") (pintype "passive"))
      (node (ref "X22") (pin "9") (pinfunction "GND_9") (pintype "passive"))
      (node (ref "X23") (pin "1") (pinfunction "GND_1") (pintype "passive"))
      (node (ref "X23") (pin "10") (pinfunction "GND_10") (pintype "passive"))
      (node (ref "X23") (pin "12") (pinfunction "GND_12") (pintype "passive"))
      (node (ref "X23") (pin "13") (pinfunction "GND_13") (pintype "passive"))
      (node (ref "X23") (pin "14") (pinfunction "GND_14") (pintype "passive"))
      (node (ref "X23") (pin "3") (pinfunction "GND_3") (pintype "passive"))
      (node (ref "X23") (pin "4") (pinfunction "GND_4") (pintype "passive"))
      (node (ref "X23") (pin "5") (pinfunction "GND_5") (pintype "passive"))
      (node (ref "X23") (pin "7") (pinfunction "GND_7") (pintype "passive"))
      (node (ref "X23") (pin "8") (pinfunction "GND_8") (pintype "passive"))
      (node (ref "X24") (pin "10") (pinfunction "GND_10") (pintype "passive"))
      (node (ref "X24") (pin "11") (pinfunction "GND_11") (pintype "passive"))
      (node (ref "X24") (pin "12") (pinfunction "GND_12") (pintype "passive"))
      (node (ref "X24") (pin "2") (pinfunction "GND_2") (pintype "passive"))
      (node (ref "X24") (pin "3") (pinfunction "GND_3") (pintype "passive"))
      (node (ref "X24") (pin "4") (pinfunction "GND_4") (pintype "passive"))
      (node (ref "X24") (pin "5") (pinfunction "GND_5") (pintype "passive"))
      (node (ref "X24") (pin "6") (pinfunction "GND_6") (pintype "passive"))
      (node (ref "X24") (pin "7") (pinfunction "GND_7") (pintype "passive"))
      (node (ref "X24") (pin "9") (pinfunction "GND_9") (pintype "passive"))
      (node (ref "X25") (pin "1") (pinfunction "GND_1") (pintype "passive"))
      (node (ref "X25") (pin "10") (pinfunction "GND_10") (pintype "passive"))
      (node (ref "X25") (pin "12") (pinfunction "GND_12") (pintype "passive"))
      (node (ref "X25") (pin "13") (pinfunction "GND_13") (pintype "passive"))
      (node (ref "X25") (pin "14") (pinfunction "GND_14") (pintype "passive"))
      (node (ref "X25") (pin "3") (pinfunction "GND_3") (pintype "passive"))
      (node (ref "X25") (pin "4") (pinfunction "GND_4") (pintype "passive"))
      (node (ref "X25") (pin "5") (pinfunction "GND_5") (pintype "passive"))
      (node (ref "X25") (pin "7") (pinfunction "GND_7") (pintype "passive"))
      (node (ref "X25") (pin "8") (pinfunction "GND_8") (pintype "passive"))
      (node (ref "X26") (pin "10") (pinfunction "GND_10") (pintype "passive"))
      (node (ref "X26") (pin "11") (pinfunction "GND_11") (pintype "passive"))
      (node (ref "X26") (pin "12") (pinfunction "GND_12") (pintype "passive"))
      (node (ref "X26") (pin "2") (pinfunction "GND_2") (pintype "passive"))
      (node (ref "X26") (pin "3") (pinfunction "GND_3") (pintype "passive"))
      (node (ref "X26") (pin "4") (pinfunction "GND_4") (pintype "passive"))
      (node (ref "X26") (pin "5") (pinfunction "GND_5") (pintype "passive"))
      (node (ref "X26") (pin "6") (pinfunction "GND_6") (pintype "passive"))
      (node (ref "X26") (pin "7") (pinfunction "GND_7") (pintype "passive"))
      (node (ref "X26") (pin "9") (pinfunction "GND_9") (pintype "passive"))
      (node (ref "X27") (pin "1") (pinfunction "GND_1") (pintype "passive"))
      (node (ref "X27") (pin "10") (pinfunction "GND_10") (pintype "passive"))
      (node (ref "X27") (pin "12") (pinfunction "GND_12") (pintype "passive"))
      (node (ref "X27") (pin "13") (pinfunction "GND_13") (pintype "passive"))
      (node (ref "X27") (pin "14") (pinfunction "GND_14") (pintype "passive"))
      (node (ref "X27") (pin "3") (pinfunction "GND_3") (pintype "passive"))
      (node (ref "X27") (pin "4") (pinfunction "GND_4") (pintype "passive"))
      (node (ref "X27") (pin "5") (pinfunction "GND_5") (pintype "passive"))
      (node (ref "X27") (pin "7") (pinfunction "GND_7") (pintype "passive"))
      (node (ref "X27") (pin "8") (pinfunction "GND_8") (pintype "passive"))
      (node (ref "X3") (pin "2") (pinfunction "GND_2") (pintype "passive"))
      (node (ref "X3") (pin "3") (pinfunction "GND_3") (pintype "passive"))
      (node (ref "X3") (pin "6") (pinfunction "GND_6") (pintype "passive"))
      (node (ref "X3") (pin "8") (pinfunction "GND_8") (pintype "passive"))
      (node (ref "X4") (pin "2") (pinfunction "GND_2") (pintype "passive"))
      (node (ref "X4") (pin "3") (pinfunction "GND_3") (pintype "passive"))
      (node (ref "X4") (pin "6") (pinfunction "GND_6") (pintype "passive"))
      (node (ref "X4") (pin "8") (pinfunction "GND_8") (pintype "passive"))
      (node (ref "X5") (pin "2") (pinfunction "GND_2") (pintype "passive"))
      (node (ref "X5") (pin "3") (pinfunction "GND_3") (pintype "passive"))
      (node (ref "X5") (pin "6") (pinfunction "GND_6") (pintype "passive"))
      (node (ref "X5") (pin "8") (pinfunction "GND_8") (pintype "passive"))
      (node (ref "X6") (pin "2") (pinfunction "GND_2") (pintype "passive"))
      (node (ref "X6") (pin "3") (pinfunction "GND_3") (pintype "passive"))
      (node (ref "X6") (pin "5") (pinfunction "GND_5") (pintype "passive"))
      (node (ref "X6") (pin "7") (pinfunction "GND_7") (pintype "passive"))
      (node (ref "X6") (pin "8") (pinfunction "GND_8") (pintype "passive"))
      (node (ref "X7") (pin "2") (pinfunction "GND_2") (pintype "passive"))
      (node (ref "X7") (pin "3") (pinfunction "GND_3") (pintype "passive"))
      (node (ref "X7") (pin "5") (pinfunction "GND_5") (pintype "passive"))
      (node (ref "X7") (pin "7") (pinfunction "GND_7") (pintype "passive"))
      (node (ref "X7") (pin "8") (pinfunction "GND_8") (pintype "passive"))
      (node (ref "X8") (pin "11") (pinfunction "GND_11") (pintype "passive"))
      (node (ref "X8") (pin "16") (pinfunction "GND_16") (pintype "passive"))
      (node (ref "X8") (pin "24") (pinfunction "GND_24") (pintype "passive"))
      (node (ref "X8") (pin "29") (pinfunction "GND_29") (pintype "passive"))
      (node (ref "X8") (pin "34") (pinfunction "GND_34") (pintype "passive"))
      (node (ref "X8") (pin "38") (pinfunction "GND_38") (pintype "passive"))
      (node (ref "X8") (pin "39") (pinfunction "GND_39") (pintype "passive"))
      (node (ref "X8") (pin "6") (pinfunction "GND_6") (pintype "passive"))
      (node (ref "X9") (pin "11") (pinfunction "GND_11") (pintype "passive"))
      (node (ref "X9") (pin "16") (pinfunction "GND_16") (pintype "passive"))
      (node (ref "X9") (pin "24") (pinfunction "GND_24") (pintype "passive"))
      (node (ref "X9") (pin "29") (pinfunction "GND_29") (pintype "passive"))
      (node (ref "X9") (pin "34") (pinfunction "GND_34") (pintype "passive"))
      (node (ref "X9") (pin "38") (pinfunction "GND_38") (pintype "passive"))
      (node (ref "X9") (pin "39") (pinfunction "GND_39") (pintype "passive"))
      (node (ref "X9") (pin "6") (pinfunction "GND_6") (pintype "passive"))
    )
    (net (code "101") (name "Net-(J10-Pad1)") (class "Default")
      (node (ref "J10") (pin "1") (pinfunction "1_1") (pintype "passive"))
      (node (ref "P1") (pin "1") (pinfunction "1_1") (pintype "passive"))
      (node (ref "P1") (pin "3") (pinfunction "3_3") (pintype "passive"))
      (node (ref "P1") (pin "5") (pinfunction "5_5") (pintype "passive"))
    )
    (net (code "102") (name "Net-(X27-HIGH)") (class "Default")
      (node (ref "P6") (pin "3") (pinfunction "3_3") (pintype "passive"))
      (node (ref "X27") (pin "9") (pinfunction "HIGH_9") (pintype "passive"))
    )
    (net (code "103") (name "Net-(X27-LOW)") (class "Default")
      (node (ref "P6") (pin "1") (pinfunction "1_1") (pintype "passive"))
      (node (ref "X27") (pin "11") (pinfunction "LOW_11") (pintype "passive"))
    )
    (net (code "104") (name "unconnected-(P3-Pad2)") (class "Default")
      (node (ref "P3") (pin "2") (pinfunction "2_2") (pintype "passive"))
    )
    (net (code "105") (name "unconnected-(P3-Pad3)") (class "Default")
      (node (ref "P3") (pin "3") (pinfunction "3_3") (pintype "passive"))
    )
    (net (code "106") (name "unconnected-(P3-Pad4)") (class "Default")
      (node (ref "P3") (pin "4") (pinfunction "4_4") (pintype "passive"))
    )
    (net (code "107") (name "unconnected-(P3-Pad5)") (class "Default")
      (node (ref "P3") (pin "5") (pinfunction "5_5") (pintype "passive"))
    )
    (net (code "108") (name "unconnected-(P3-Pad6)") (class "Default")
      (node (ref "P3") (pin "6") (pinfunction "6_6") (pintype "passive"))
    )
    (net (code "109") (name "unconnected-(P3-Pad11)") (class "Default")
      (node (ref "P3") (pin "11") (pinfunction "11_11") (pintype "passive"))
    )
    (net (code "110") (name "unconnected-(P11-Pad3)") (class "Default")
      (node (ref "P11") (pin "3") (pinfunction "3_3") (pintype "passive"))
    )
    (net (code "111") (name "unconnected-(X8-NC-Pad1)") (class "Default")
      (node (ref "X8") (pin "1") (pinfunction "NC_1") (pintype "passive"))
    )
    (net (code "112") (name "unconnected-(X8-NC-Pad18)") (class "Default")
      (node (ref "X8") (pin "18") (pinfunction "NC_18") (pintype "passive"))
    )
    (net (code "113") (name "unconnected-(X8-NC-Pad19)") (class "Default")
      (node (ref "X8") (pin "19") (pinfunction "NC_19") (pintype "passive"))
    )
    (net (code "114") (name "unconnected-(X8-NC-Pad37)") (class "Default")
      (node (ref "X8") (pin "37") (pinfunction "NC_37") (pintype "passive"))
    )
    (net (code "115") (name "unconnected-(X9-NC-Pad1)") (class "Default")
      (node (ref "X9") (pin "1") (pinfunction "NC_1") (pintype "passive"))
    )
    (net (code "116") (name "unconnected-(X9-NC-Pad18)") (class "Default")
      (node (ref "X9") (pin "18") (pinfunction "NC_18") (pintype "passive"))
    )
    (net (code "117") (name "unconnected-(X9-NC-Pad19)") (class "Default")
      (node (ref "X9") (pin "19") (pinfunction "NC_19") (pintype "passive"))
    )
    (net (code "118") (name "unconnected-(X9-NC-Pad37)") (class "Default")
      (node (ref "X9") (pin "37") (pinfunction "NC_37") (pintype "passive"))
    )
    (net (code "119") (name "unconnected-(X14-R1_2-Pad9)") (class "Default")
      (node (ref "X14") (pin "9") (pinfunction "R1_2_9") (pintype "passive"))
    )
    (net (code "120") (name "unconnected-(X14-R1_3-Pad10)") (class "Default")
      (node (ref "X14") (pin "10") (pinfunction "R1_3_10") (pintype "passive"))
    )
    (net (code "121") (name "unconnected-(X14-R1_4-Pad11)") (class "Default")
      (node (ref "X14") (pin "11") (pinfunction "R1_4_11") (pintype "passive"))
    )
    (net (code "122") (name "unconnected-(X14-R1_5-Pad4)") (class "Default")
      (node (ref "X14") (pin "4") (pinfunction "R1_5_4") (pintype "passive"))
    )
    (net (code "123") (name "unconnected-(X14-R2_2-Pad14)") (class "Default")
      (node (ref "X14") (pin "14") (pinfunction "R2_2_14") (pintype "passive"))
    )
    (net (code "124") (name "unconnected-(X14-R2_7-Pad3)") (class "Default")
      (node (ref "X14") (pin "3") (pinfunction "R2_7_3") (pintype "passive"))
    )
    (net (code "125") (name "unconnected-(X15-2-Pad3)") (class "Default")
      (node (ref "X15") (pin "3") (pinfunction "2_3") (pintype "passive"))
    )
    (net (code "126") (name "unconnected-(X16-0-Pad1)") (class "Default")
      (node (ref "X16") (pin "1") (pinfunction "0_1") (pintype "passive"))
    )
    (net (code "127") (name "unconnected-(X18-R1_2-Pad9)") (class "Default")
      (node (ref "X18") (pin "9") (pinfunction "R1_2_9") (pintype "passive"))
    )
    (net (code "128") (name "unconnected-(X18-R1_3-Pad10)") (class "Default")
      (node (ref "X18") (pin "10") (pinfunction "R1_3_10") (pintype "passive"))
    )
    (net (code "129") (name "unconnected-(X18-R1_4-Pad11)") (class "Default")
      (node (ref "X18") (pin "11") (pinfunction "R1_4_11") (pintype "passive"))
    )
    (net (code "130") (name "unconnected-(X18-R1_5-Pad4)") (class "Default")
      (node (ref "X18") (pin "4") (pinfunction "R1_5_4") (pintype "passive"))
    )
    (net (code "131") (name "unconnected-(X18-R2_2-Pad14)") (class "Default")
      (node (ref "X18") (pin "14") (pinfunction "R2_2_14") (pintype "passive"))
    )
    (net (code "132") (name "unconnected-(X18-R2_7-Pad3)") (class "Default")
      (node (ref "X18") (pin "3") (pinfunction "R2_7_3") (pintype "passive"))
    )
    (net (code "133") (name "unconnected-(X20-2-Pad3)") (class "Default")
      (node (ref "X20") (pin "3") (pinfunction "2_3") (pintype "passive"))
    )
    (net (code "134") (name "unconnected-(X21-R1_2-Pad9)") (class "Default")
      (node (ref "X21") (pin "9") (pinfunction "R1_2_9") (pintype "passive"))
    )
    (net (code "135") (name "unconnected-(X21-R1_3-Pad10)") (class "Default")
      (node (ref "X21") (pin "10") (pinfunction "R1_3_10") (pintype "passive"))
    )
    (net (code "136") (name "unconnected-(X21-R1_4-Pad11)") (class "Default")
      (node (ref "X21") (pin "11") (pinfunction "R1_4_11") (pintype "passive"))
    )
    (net (code "137") (name "unconnected-(X21-R1_5-Pad4)") (class "Default")
      (node (ref "X21") (pin "4") (pinfunction "R1_5_4") (pintype "passive"))
    )
    (net (code "138") (name "unconnected-(X21-R2_2-Pad14)") (class "Default")
      (node (ref "X21") (pin "14") (pinfunction "R2_2_14") (pintype "passive"))
    )
    (net (code "139") (name "unconnected-(X21-R2_7-Pad3)") (class "Default")
      (node (ref "X21") (pin "3") (pinfunction "R2_7_3") (pintype "passive"))
    )
    (net (code "140") (name "unconnected-(X28-+V-Pad3)") (class "Default")
      (node (ref "X28") (pin "3") (pinfunction "+V_3") (pintype "passive"))
    )
  )
)
